# ProProject_3rd-Chebyshev-BPF-3_5-54M-202.net
KiCad netlist of a schematic drawn in EasyEDA Pro
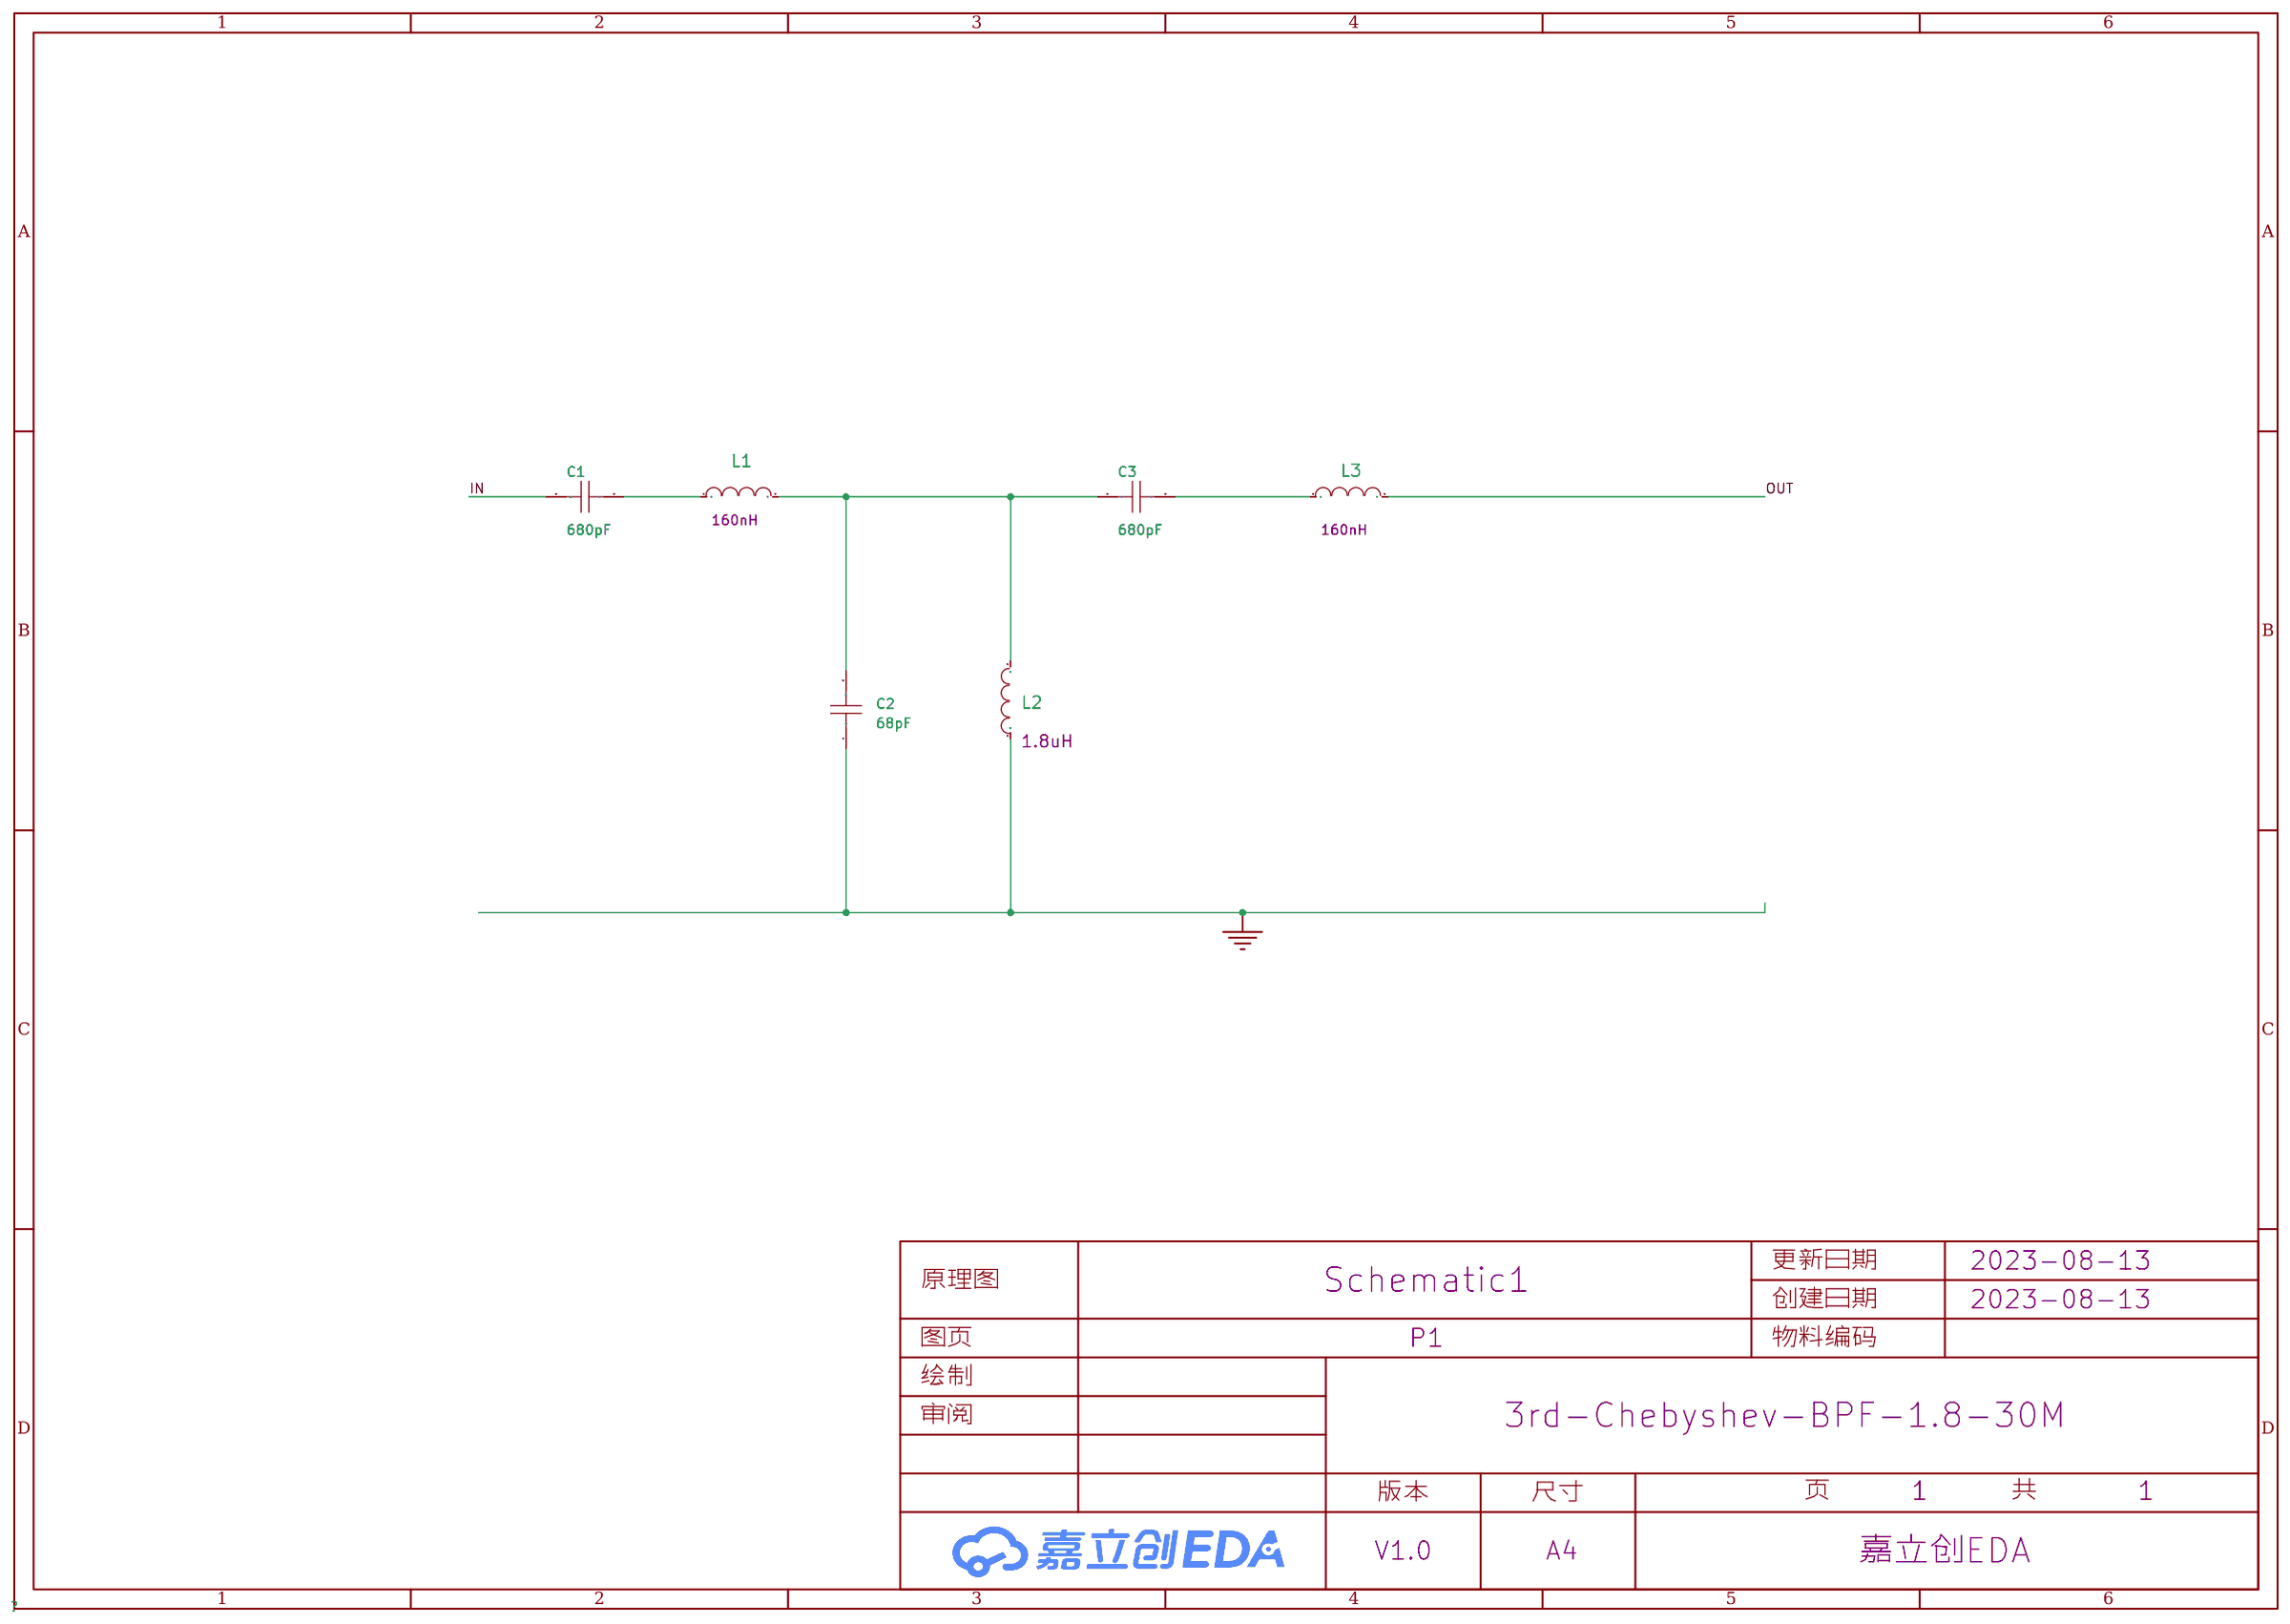
[diagram p0: schematic sheet]

(export (version "E")
  (design (tool "Eeschema 10.0.6"))
  (components
    (comp (ref "C1")
      (value "680pF")
      (footprint "easyedapro:CAP-TH_L8.0-W4.0-P5.00-D1.2")
      (description "容值:820pF;精度:±10%;额定电压:2kV;温度系数:Y5P;")
      (fields (field (name "Manufacturer Part") "CT81-M7Y5P1B821KSE") (field (name "Manufacturer") "FH(风华)"))
      (libsource (lib "easyedapro") (part "CT81-M7Y5P1B821KSE"))
    )
    (comp (ref "C2")
      (value "68pF")
      (footprint "easyedapro:CAP-TH_L8.0-W4.0-P5.00-D1.2")
      (description "容值:820pF;精度:±10%;额定电压:2kV;温度系数:Y5P;")
      (fields (field (name "Manufacturer Part") "CT81-M7Y5P1B821KSE") (field (name "Manufacturer") "FH(风华)"))
      (libsource (lib "easyedapro") (part "CT81-M7Y5P1B821KSE"))
    )
    (comp (ref "C3")
      (value "680pF")
      (footprint "easyedapro:CAP-TH_L8.0-W4.0-P5.00-D1.2")
      (description "容值:820pF;精度:±10%;额定电压:2kV;温度系数:Y5P;")
      (fields (field (name "Manufacturer Part") "CT81-M7Y5P1B821KSE") (field (name "Manufacturer") "FH(风华)"))
      (libsource (lib "easyedapro") (part "CT81-M7Y5P1B821KSE"))
    )
    (comp (ref "L1")
      (value "~")
      (fields (field (name "Inductance") "160nH"))
      (libsource (lib "easyedapro") (part "直插电感8mm"))
    )
    (comp (ref "L2")
      (value "~")
      (fields (field (name "Inductance") "1.8uH"))
      (libsource (lib "easyedapro") (part "直插电感8mm"))
    )
    (comp (ref "L3")
      (value "~")
      (fields (field (name "Inductance") "160nH"))
      (libsource (lib "easyedapro") (part "直插电感8mm"))
    )
  )
  (nets
    (net (code "1") (name "/IN") (class "Default")
      (node (ref "C1") (pin "2") (pinfunction "2_2") (pintype "input"))
    )
    (net (code "2") (name "/OUT") (class "Default")
      (node (ref "L3") (pin "2") (pinfunction "2_2") (pintype "input"))
    )
    (net (code "3") (name "GND") (class "Default")
      (node (ref "C2") (pin "1") (pinfunction "1_1") (pintype "input"))
      (node (ref "L2") (pin "1") (pinfunction "1_1") (pintype "input"))
    )
    (net (code "4") (name "Net-(C1-Pad1)") (class "Default")
      (node (ref "C1") (pin "1") (pinfunction "1_1") (pintype "input"))
      (node (ref "L1") (pin "1") (pinfunction "1_1") (pintype "input"))
    )
    (net (code "5") (name "Net-(C2-Pad2)") (class "Default")
      (node (ref "C2") (pin "2") (pinfunction "2_2") (pintype "input"))
      (node (ref "C3") (pin "2") (pinfunction "2_2") (pintype "input"))
      (node (ref "L1") (pin "2") (pinfunction "2_2") (pintype "input"))
      (node (ref "L2") (pin "2") (pinfunction "2_2") (pintype "input"))
    )
    (net (code "6") (name "Net-(C3-Pad1)") (class "Default")
      (node (ref "C3") (pin "1") (pinfunction "1_1") (pintype "input"))
      (node (ref "L3") (pin "1") (pinfunction "1_1") (pintype "input"))
    )
  )
)
